# power.net
KiCad netlist of a schematic drawn in Altium Designer
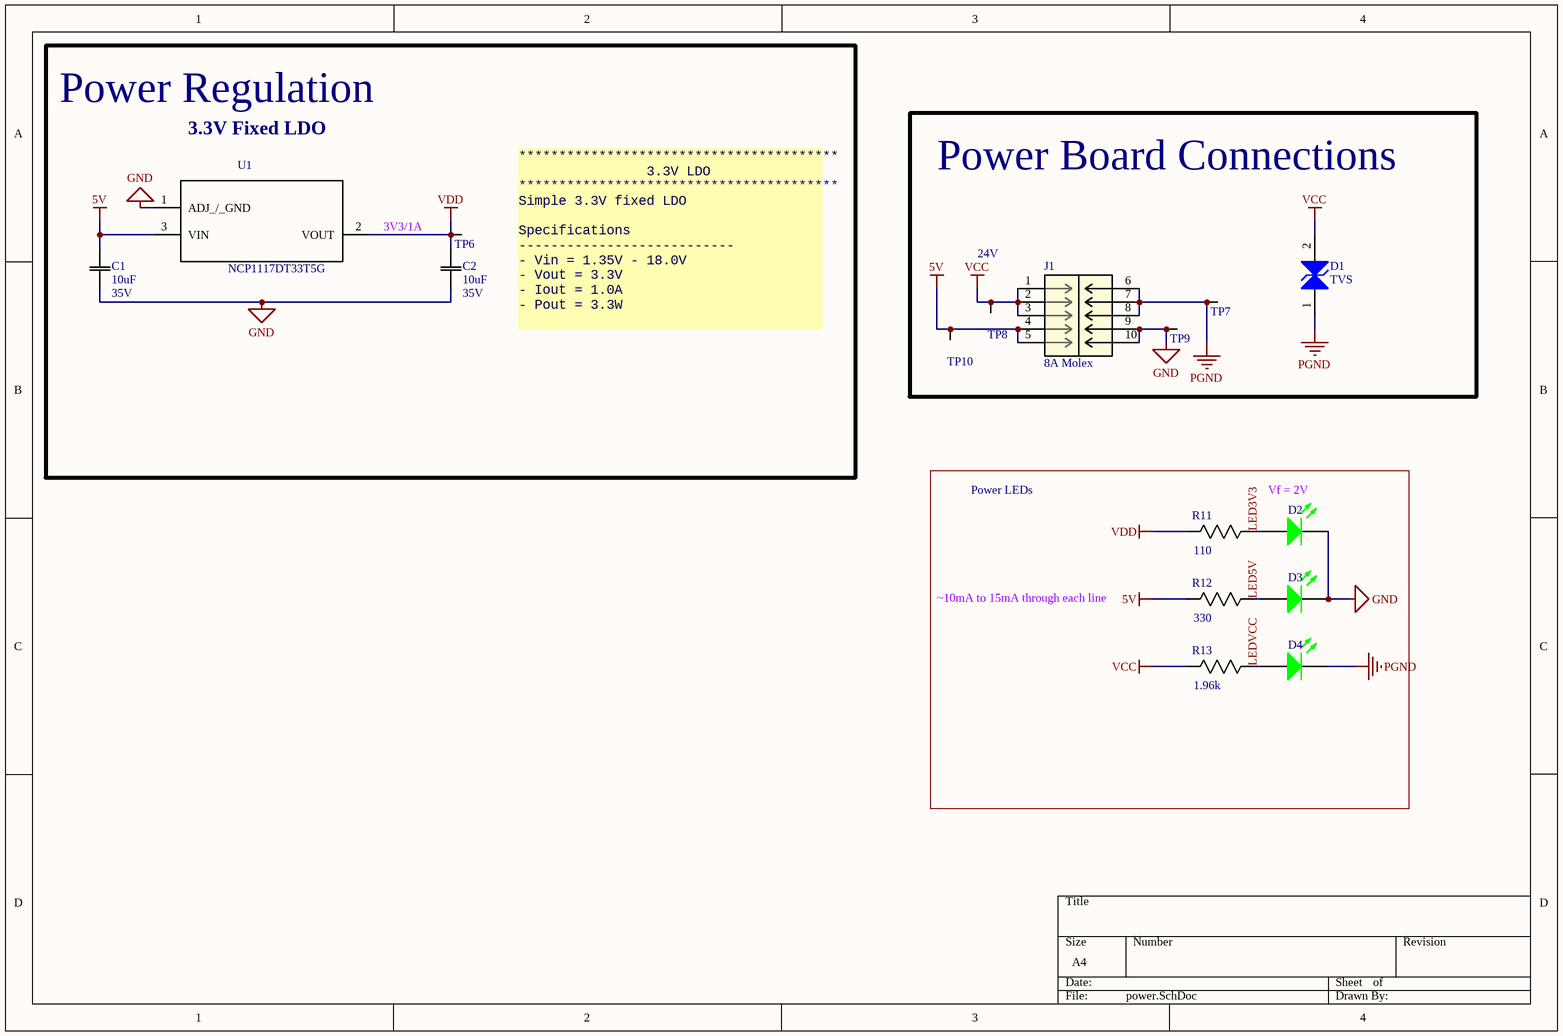
[diagram p0: power.SchDoc]

(export (version "E")
  (design (tool "Eeschema 10.0.6"))
  (components
    (comp (ref "C1")
      (value "10uF")
      (footprint "0805")
      (description "Default Symbol for Capacitors")
      (fields
        (field (name "TOLERANCE") "10%")
        (field (name "RATING") "35V")
        (field (name "PART NUMBER") "CAP 10uF 35V_1")
      )
      (libsource (lib "capacitor_library") (part "CAP_Default"))
    )
    (comp (ref "C2")
      (value "10uF")
      (footprint "0805")
      (description "Default Symbol for Capacitors")
      (fields
        (field (name "TOLERANCE") "10%")
        (field (name "RATING") "35V")
        (field (name "PART NUMBER") "CAP 10uF 35V_1")
      )
      (libsource (lib "capacitor_library") (part "CAP_Default"))
    )
    (comp (ref "D1")
      (value "TVS")
      (footprint "DO-214AC, SMA")
      (description "TVS DIODE 26V 53.5V SMA")
      (fields (field (name "PART NUMBER") "DIODE TVS 26VWM 53.5VC SMA") (field (name "POWER") "400W"))
      (libsource (lib "Diode_Library") (part "DIODE TVS 26VWM 53.5VC SMA"))
    )
    (comp (ref "D2")
      (value "0603 2V")
      (footprint "0603 - LED")
      (description "LED Uni-Color Green 574nm 2-Pin Chip LED T/R")
      (fields (field (name "PART NUMBER") "LED GREEN SMD 0603"))
      (libsource (lib "Diode_Library") (part "LED GREEN SMD 0603"))
    )
    (comp (ref "D3")
      (value "0603 2V")
      (footprint "0603 - LED")
      (description "LED Uni-Color Green 574nm 2-Pin Chip LED T/R")
      (fields (field (name "PART NUMBER") "LED GREEN SMD 0603"))
      (libsource (lib "Diode_Library") (part "LED GREEN SMD 0603"))
    )
    (comp (ref "D4")
      (value "0603 2V")
      (footprint "0603 - LED")
      (description "LED Uni-Color Green 574nm 2-Pin Chip LED T/R")
      (fields (field (name "PART NUMBER") "LED GREEN SMD 0603"))
      (libsource (lib "Diode_Library") (part "LED GREEN SMD 0603"))
    )
    (comp (ref "J1")
      (value "8A Molex")
      (footprint "MOLEX_0430451012")
      (description "CONN HEADER VERT 10POS 3MM")
      (fields (field (name "PART NUMBER") "CN HDR 10POS MOLEX 0430451012"))
      (libsource (lib "Connector_Library") (part "CN HDR 10POS MOLEX 0430451012"))
    )
    (comp (ref "R11")
      (value "110")
      (footprint "0603")
      (description "Default Resistor Symbol")
      (fields (field (name "TOLERANCE") "1%") (field (name "PART NUMBER") "RES 110.0 1/8W - 1%"))
      (libsource (lib "Resistor_Library") (part "RES_DEFAULT"))
    )
    (comp (ref "R12")
      (value "330")
      (footprint "0603")
      (description "Default Resistor Symbol")
      (fields (field (name "TOLERANCE") "5%") (field (name "PART NUMBER") "RES 330.0 1/8W - 5%"))
      (libsource (lib "") (part "RES_DEFAULT_1"))
    )
    (comp (ref "R13")
      (value "1.96k")
      (footprint "0603")
      (description "Default Resistor Symbol")
      (fields (field (name "TOLERANCE") "1%") (field (name "PART NUMBER") "RES 1.96k 1/8W"))
      (libsource (lib "") (part "RES_DEFAULT_1"))
    )
    (comp (ref "TP6")
      (value "VDD")
      (footprint "TP")
      (fields (field (name "PART NUMBER") "Test Point (Via)"))
      (libsource (lib "IC_Library") (part "Test Point (Via)"))
    )
    (comp (ref "TP7")
      (value "PGND")
      (footprint "TP")
      (fields (field (name "PART NUMBER") "Test Point (Via)"))
      (libsource (lib "IC_Library") (part "Test Point (Via)"))
    )
    (comp (ref "TP8")
      (value "VCC")
      (footprint "TP")
      (fields (field (name "PART NUMBER") "Test Point (Via)"))
      (libsource (lib "IC_Library") (part "Test Point (Via)"))
    )
    (comp (ref "TP9")
      (value "GND")
      (footprint "TP")
      (fields (field (name "PART NUMBER") "Test Point (Via)"))
      (libsource (lib "IC_Library") (part "Test Point (Via)"))
    )
    (comp (ref "TP10")
      (value "5V")
      (footprint "TP")
      (fields (field (name "PART NUMBER") "Test Point (Via)"))
      (libsource (lib "IC_Library") (part "Test Point (Via)"))
    )
    (comp (ref "U1")
      (value "NCP1117DT33T5G")
      (footprint "DPAK (TO-252)")
      (description "Linear Voltage Regulator IC Positive Fixed 1 Output 1A DPAK")
      (libsource (lib "IC_Library") (part "NCP1117DT33T5G"))
    )
  )
  (nets
    (net (code "1") (name "/LED3V3") (class "Default")
      (node (ref "D2") (pin "1") (pinfunction "A_1") (pintype "passive"))
      (node (ref "R11") (pin "1") (pinfunction "R1_1") (pintype "passive"))
    )
    (net (code "2") (name "/LED5V") (class "Default")
      (node (ref "D3") (pin "1") (pinfunction "A_1") (pintype "passive"))
      (node (ref "R12") (pin "1") (pinfunction "R1_1") (pintype "passive"))
    )
    (net (code "3") (name "/LEDVCC") (class "Default")
      (node (ref "D4") (pin "1") (pinfunction "A_1") (pintype "passive"))
      (node (ref "R13") (pin "1") (pinfunction "R1_1") (pintype "passive"))
    )
    (net (code "4") (name "5V") (class "Default")
      (node (ref "C1") (pin "2") (pinfunction "C2_2") (pintype "passive"))
      (node (ref "J1") (pin "4") (pinfunction "4_4") (pintype "passive"))
      (node (ref "J1") (pin "5") (pinfunction "5_5") (pintype "passive"))
      (node (ref "R12") (pin "2") (pinfunction "R2_2") (pintype "passive"))
      (node (ref "TP10") (pin "1") (pinfunction "1_1") (pintype "passive"))
      (node (ref "U1") (pin "3") (pinfunction "VIN_3") (pintype "power_in"))
    )
    (net (code "5") (name "GND") (class "Default")
      (node (ref "C1") (pin "1") (pinfunction "C1_1") (pintype "passive"))
      (node (ref "C2") (pin "1") (pinfunction "C1_1") (pintype "passive"))
      (node (ref "D2") (pin "2") (pinfunction "K_2") (pintype "passive"))
      (node (ref "D3") (pin "2") (pinfunction "K_2") (pintype "passive"))
      (node (ref "J1") (pin "10") (pinfunction "10_10") (pintype "passive"))
      (node (ref "J1") (pin "9") (pinfunction "9_9") (pintype "passive"))
      (node (ref "TP9") (pin "1") (pinfunction "1_1") (pintype "passive"))
      (node (ref "U1") (pin "1") (pinfunction "ADJ_/_GND_1") (pintype "power_in"))
    )
    (net (code "6") (name "PGND") (class "Default")
      (node (ref "D1") (pin "1") (pinfunction "K_1") (pintype "passive"))
      (node (ref "D4") (pin "2") (pinfunction "K_2") (pintype "passive"))
      (node (ref "J1") (pin "6") (pinfunction "6_6") (pintype "passive"))
      (node (ref "J1") (pin "7") (pinfunction "7_7") (pintype "passive"))
      (node (ref "J1") (pin "8") (pinfunction "8_8") (pintype "passive"))
      (node (ref "TP7") (pin "1") (pinfunction "1_1") (pintype "passive"))
    )
    (net (code "7") (name "VCC") (class "Default")
      (node (ref "D1") (pin "2") (pinfunction "A_2") (pintype "passive"))
      (node (ref "J1") (pin "1") (pinfunction "1_1") (pintype "passive"))
      (node (ref "J1") (pin "2") (pinfunction "2_2") (pintype "passive"))
      (node (ref "J1") (pin "3") (pinfunction "3_3") (pintype "passive"))
      (node (ref "R13") (pin "2") (pinfunction "R2_2") (pintype "passive"))
      (node (ref "TP8") (pin "1") (pinfunction "1_1") (pintype "passive"))
    )
    (net (code "8") (name "VDD") (class "Default")
      (node (ref "C2") (pin "2") (pinfunction "C2_2") (pintype "passive"))
      (node (ref "R11") (pin "2") (pinfunction "R2_2") (pintype "passive"))
      (node (ref "TP6") (pin "1") (pinfunction "1_1") (pintype "passive"))
      (node (ref "U1") (pin "2") (pinfunction "VOUT_2") (pintype "power_in"))
    )
  )
)
